# Schematic.net
KiCad netlist of a schematic drawn in EasyEDA
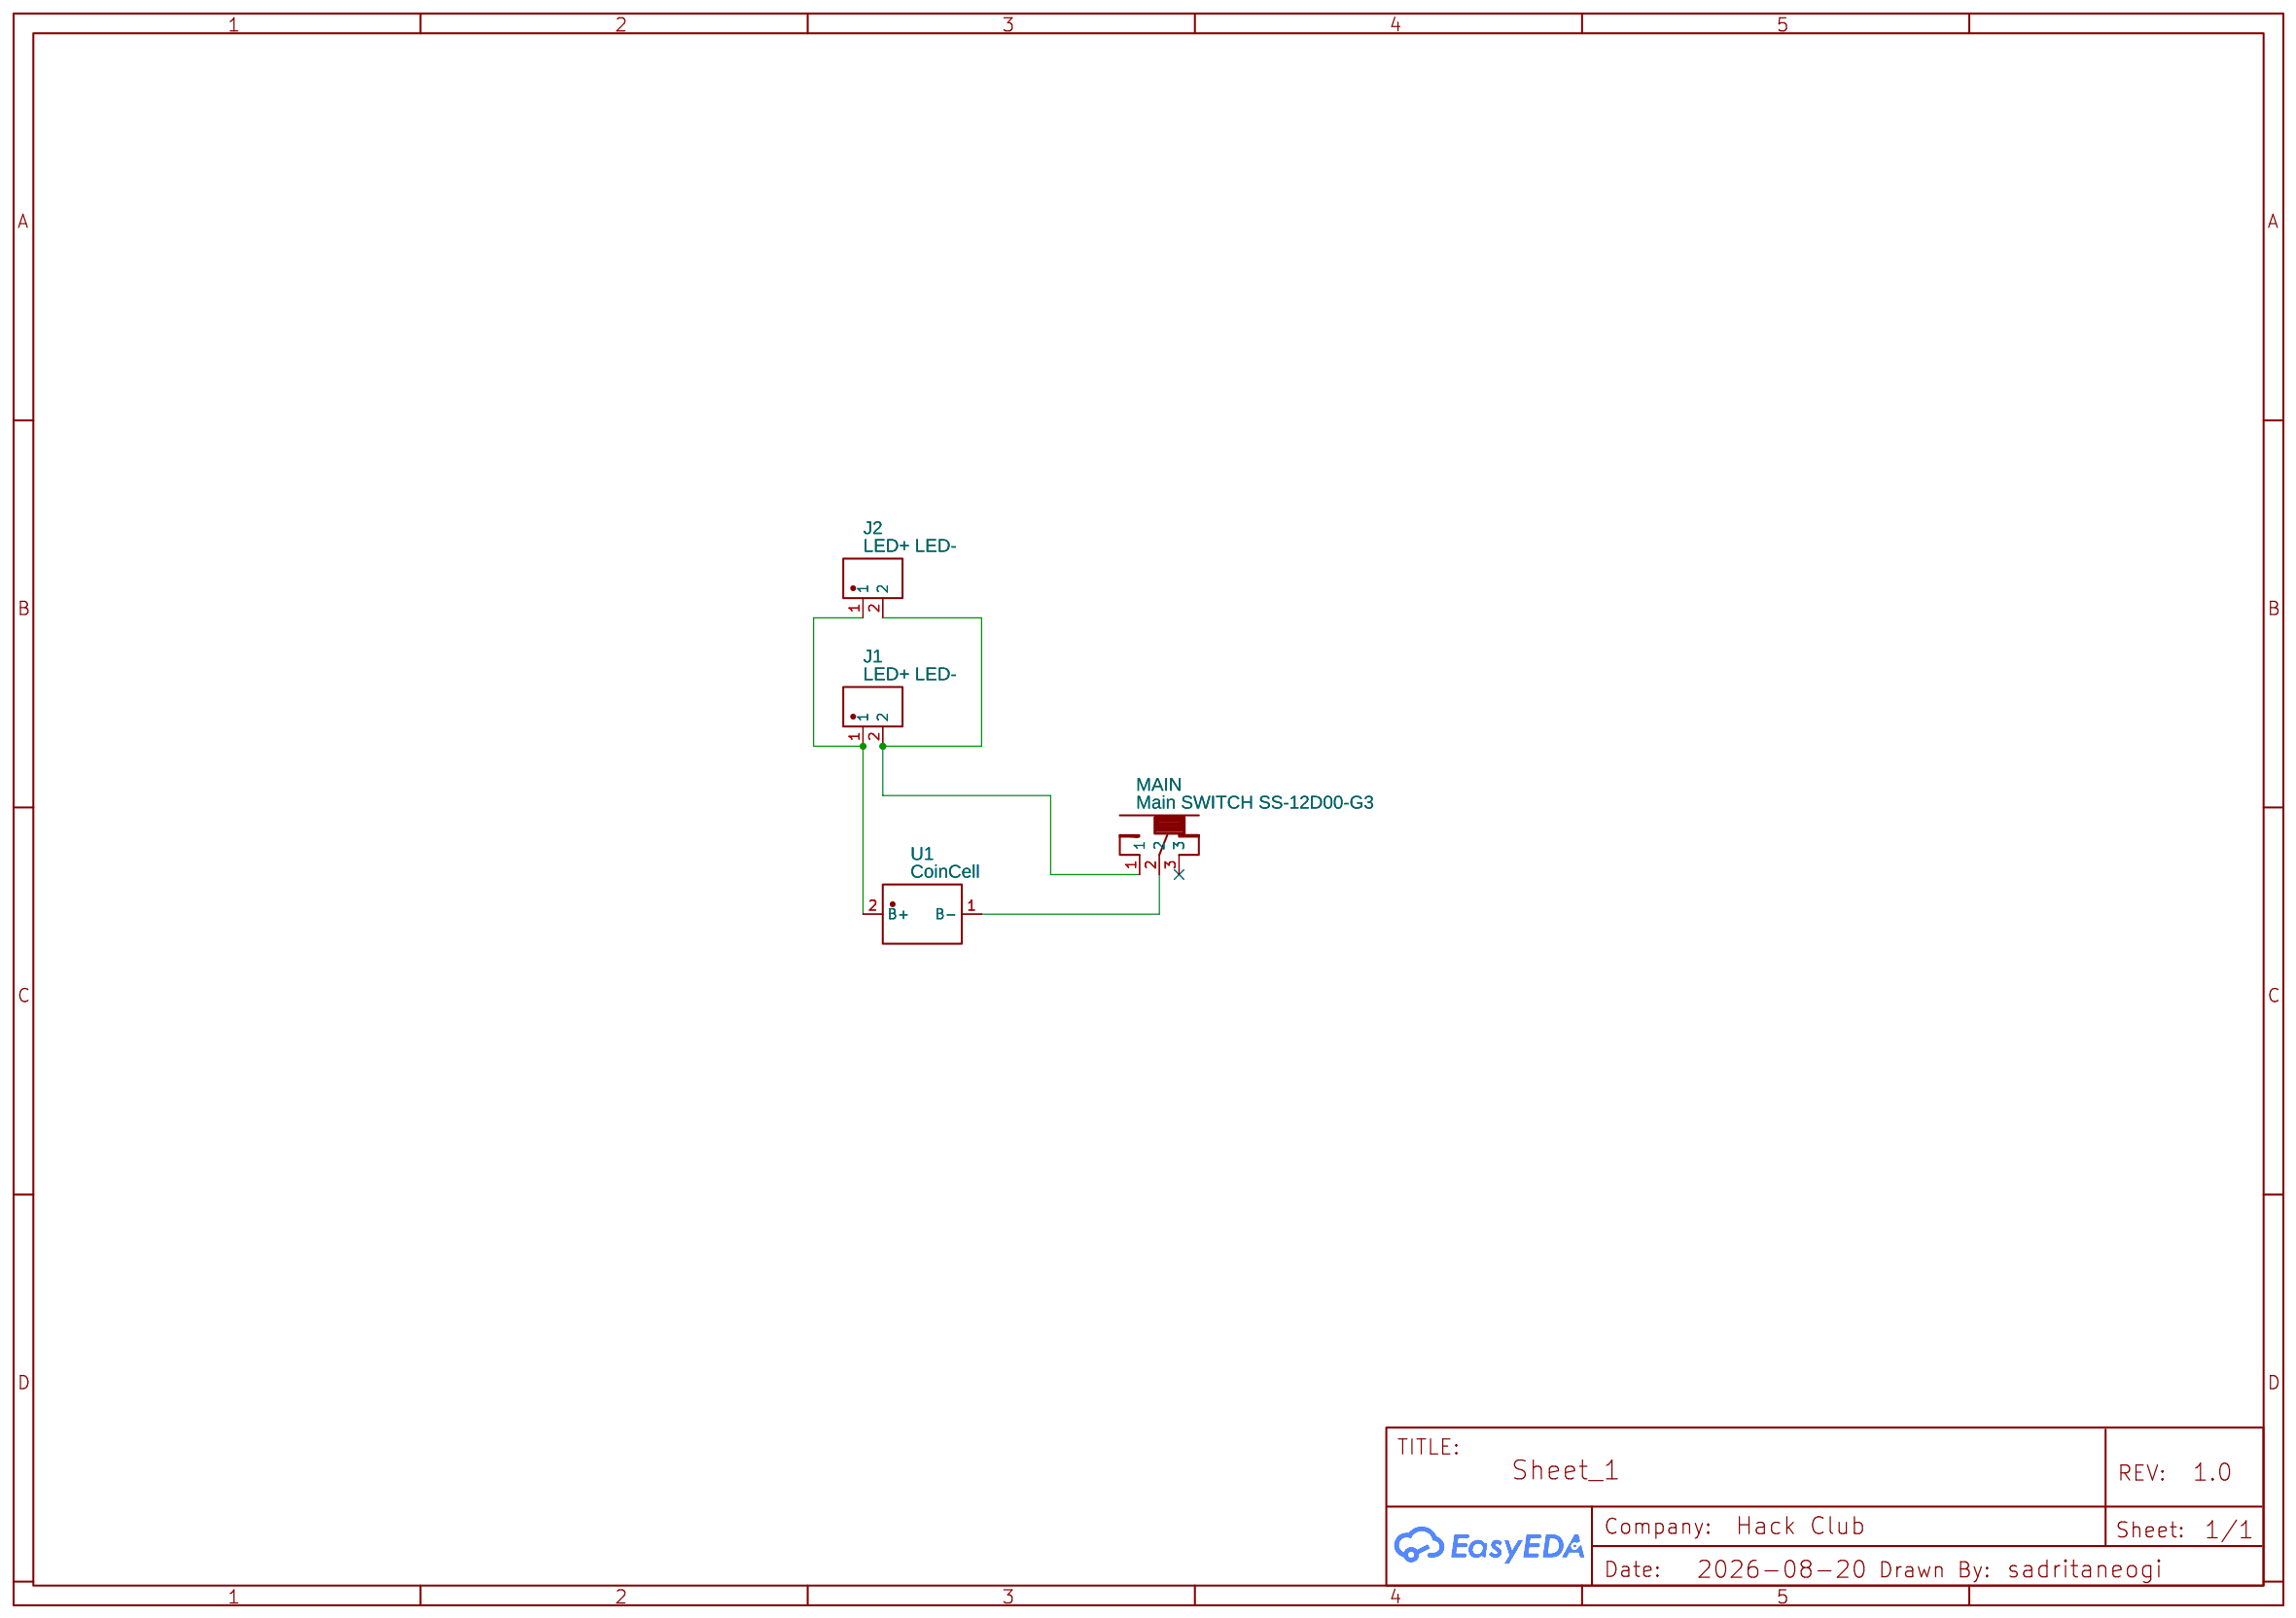
[diagram p0: schematic sheet]

(export (version "E")
  (design (tool "Eeschema 10.0.6"))
  (components
    (comp (ref "J1")
      (value "LED+ LED-")
      (fields
        (field (name "Manufacturer Part") "PH2.54-1X2P-H25")
        (field (name "Manufacturer") "JXTCONN(聚兴泰)")
      )
      (libsource (lib "") (part "LED+ LED-"))
    )
    (comp (ref "J2")
      (value "LED+ LED-")
      (fields
        (field (name "Manufacturer Part") "PH2.54-1X2P-H25")
        (field (name "Manufacturer") "JXTCONN(聚兴泰)")
      )
      (libsource (lib "") (part "LED+ LED-"))
    )
    (comp (ref "MAIN")
      (value "Main SWITCH SS-12D00-G3")
      (fields
        (field (name "Manufacturer Part") "TOGGLE SWITCH SS-12D00-G3")
        (field (name "Manufacturer") "Dailywell")
      )
      (libsource (lib "") (part "TOGGLE SWITCH SS-12D00-G3"))
    )
    (comp (ref "U1") (value "CoinCell") (libsource (lib "") (part "CoinCell")))
  )
  (nets
    (net (code "1") (name "Net-(J1-Pad2)") (class "Default")
      (node (ref "J1") (pin "2") (pinfunction "2_2") (pintype "unspecified"))
      (node (ref "J2") (pin "2") (pinfunction "2_2") (pintype "unspecified"))
      (node (ref "MAIN") (pin "1") (pinfunction "1_1") (pintype "unspecified"))
    )
    (net (code "2") (name "Net-(U1-B+)") (class "Default")
      (node (ref "J1") (pin "1") (pinfunction "1_1") (pintype "unspecified"))
      (node (ref "J2") (pin "1") (pinfunction "1_1") (pintype "unspecified"))
      (node (ref "U1") (pin "2") (pinfunction "B+_2") (pintype "unspecified"))
    )
    (net (code "3") (name "Net-(U1-B-)") (class "Default")
      (node (ref "MAIN") (pin "2") (pinfunction "2_2") (pintype "unspecified"))
      (node (ref "U1") (pin "1") (pinfunction "B-_1") (pintype "unspecified"))
    )
    (net (code "4") (name "unconnected-(MAIN-Pad3)") (class "Default")
      (node (ref "MAIN") (pin "3") (pinfunction "3_3") (pintype "unspecified+no_connect"))
    )
  )
)
